# boxer_sensors.net
KiCad netlist of a schematic drawn in Altium Designer
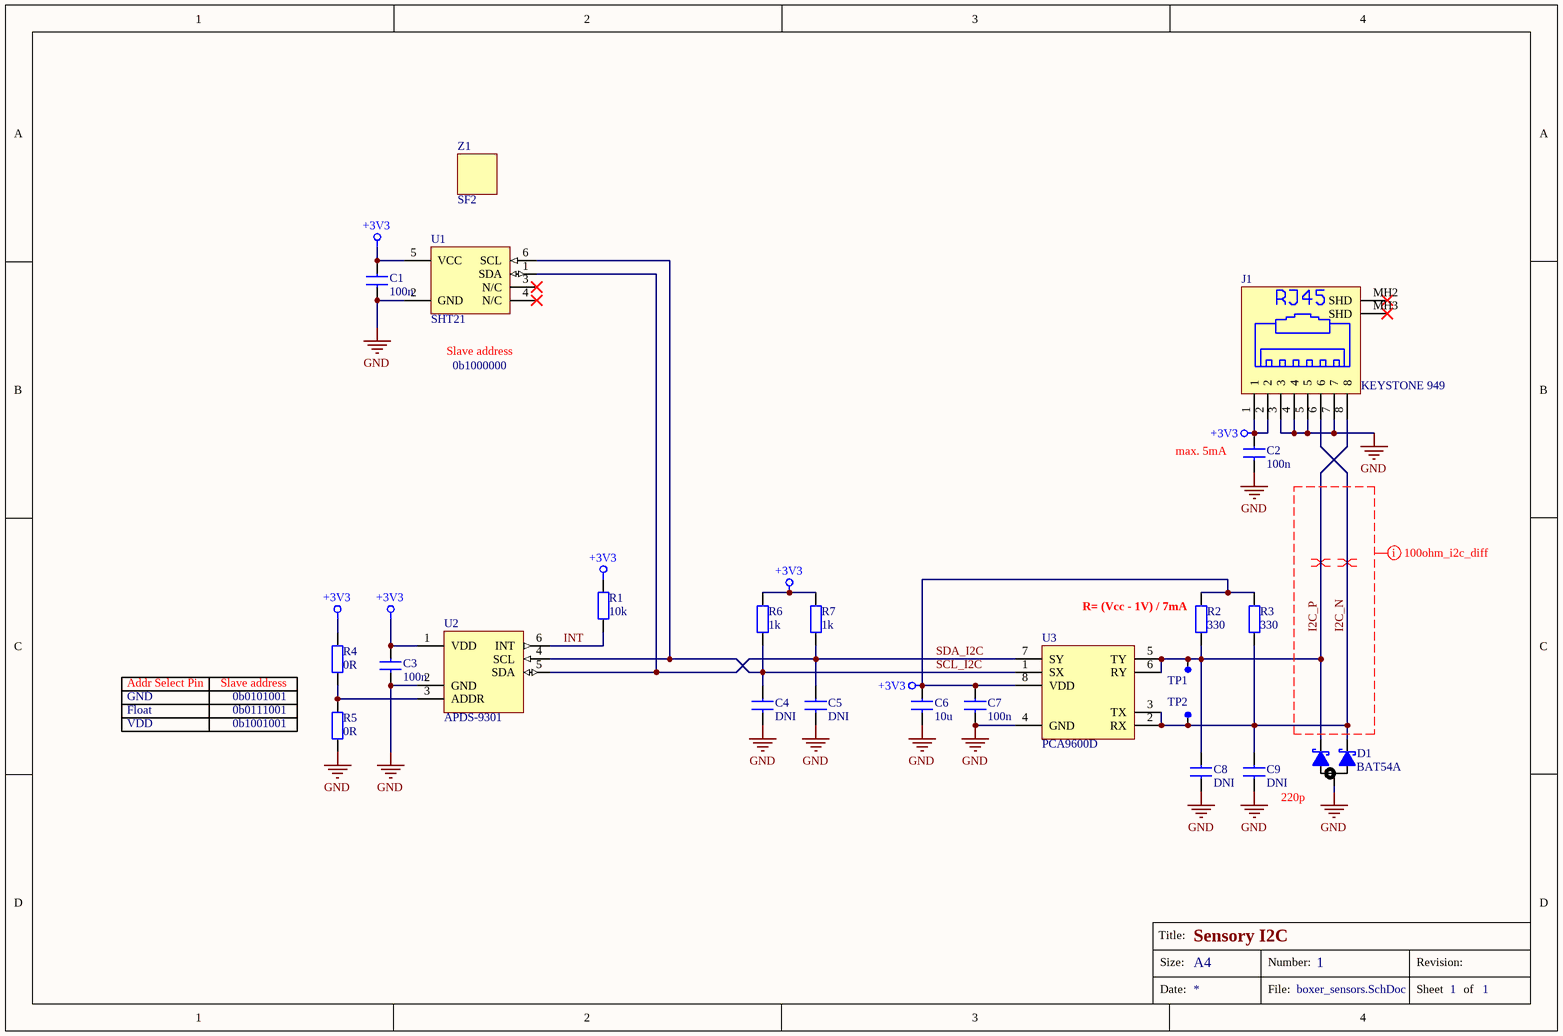
[diagram p0: boxer_sensors.SchDoc]

(export (version "E")
  (design (tool "Eeschema 10.0.6"))
  (components
    (comp (ref "C1")
      (value "100n")
      (footprint "C_0805")
      (description "Capacitor")
      (libsource (lib "boxer_pas") (part "Capacitor"))
    )
    (comp (ref "C2")
      (value "100n")
      (footprint "C_0805")
      (description "Capacitor")
      (libsource (lib "boxer_pas") (part "Capacitor"))
    )
    (comp (ref "C3")
      (value "100n")
      (footprint "C_0805")
      (description "Capacitor")
      (libsource (lib "boxer_pas") (part "Capacitor"))
    )
    (comp (ref "C4")
      (value "DNI")
      (footprint "C_0805")
      (description "Capacitor")
      (libsource (lib "boxer_pas") (part "Capacitor"))
    )
    (comp (ref "C5")
      (value "DNI")
      (footprint "C_0805")
      (description "Capacitor")
      (libsource (lib "boxer_pas") (part "Capacitor"))
    )
    (comp (ref "C6")
      (value "10u")
      (footprint "C_1206")
      (description "Capacitor")
      (libsource (lib "boxer_pas") (part "Capacitor"))
    )
    (comp (ref "C7")
      (value "100n")
      (footprint "C_0805")
      (description "Capacitor")
      (libsource (lib "boxer_pas") (part "Capacitor"))
    )
    (comp (ref "C8")
      (value "DNI")
      (footprint "C_0805")
      (description "Capacitor")
      (libsource (lib "boxer_pas") (part "Capacitor"))
    )
    (comp (ref "C9")
      (value "DNI")
      (footprint "C_0805")
      (description "Capacitor")
      (libsource (lib "boxer_pas") (part "Capacitor"))
    )
    (comp (ref "D1")
      (value "BAT54A")
      (footprint "SOT-23")
      (description "dual Schottky diode common anode")
      (libsource (lib "boxer_pas") (part "Diode Schottky3"))
    )
    (comp (ref "J1")
      (value "KEYSTONE 949")
      (footprint "PN949")
      (description "RJ45 (keystone) Jack, Vertical PCB Mount P/N 949")
      (libsource (lib "boxer_mechanical") (part "RJ45-8"))
    )
    (comp (ref "R1")
      (value "10k")
      (footprint "R_0805")
      (description "Resistor")
      (libsource (lib "boxer_pas") (part "Resistor"))
    )
    (comp (ref "R2")
      (value "330")
      (footprint "R_0805")
      (description "Resistor")
      (libsource (lib "boxer_pas") (part "Resistor"))
    )
    (comp (ref "R3")
      (value "330")
      (footprint "R_0805")
      (description "Resistor")
      (libsource (lib "boxer_pas") (part "Resistor"))
    )
    (comp (ref "R4")
      (value "0R")
      (footprint "R_0805")
      (description "Resistor")
      (libsource (lib "boxer_pas") (part "Resistor"))
    )
    (comp (ref "R5")
      (value "0R")
      (footprint "R_0805")
      (description "Resistor")
      (libsource (lib "boxer_pas") (part "Resistor"))
    )
    (comp (ref "R6")
      (value "1k")
      (footprint "R_0805")
      (description "Resistor")
      (libsource (lib "boxer_pas") (part "Resistor"))
    )
    (comp (ref "R7")
      (value "1k")
      (footprint "R_0805")
      (description "Resistor")
      (libsource (lib "boxer_pas") (part "Resistor"))
    )
    (comp (ref "TP1")
      (value "TEST PAD")
      (footprint "PIN")
      (libsource (lib "boxer_mechanical") (part "TEST_PAD"))
    )
    (comp (ref "TP2")
      (value "TEST PAD")
      (footprint "PIN")
      (libsource (lib "boxer_mechanical") (part "TEST_PAD"))
    )
    (comp (ref "U1")
      (value "SHT21")
      (footprint "DFN6")
      (description "Humidity and Temperature Sensor IC")
      (libsource (lib "boxer_ic") (part "SHT21"))
    )
    (comp (ref "U2")
      (value "APDS-9301")
      (footprint "ChipLED")
      (libsource (lib "boxer_ic") (part "APDS-9301"))
    )
    (comp (ref "U3")
      (value "PCA9600D")
      (footprint "SO8")
      (description "Dual bidirectional I2C bus buffer")
      (libsource (lib "boxer_ic") (part "PCA9600"))
    )
    (comp (ref "Z1")
      (value "SF2")
      (footprint "SF2")
      (description "SF2 Filter Cap  Filter Cap for Humidity &  Temperature Sensors SHT2x")
      (fields (field (name "Comment") "SF2 Filter Cap"))
      (libsource (lib "boxer_mechanical") (part "SF2"))
    )
  )
  (nets
    (net (code "1") (name "+3V3") (class "Default")
      (node (ref "C1") (pin "2") (pinfunction "2_2") (pintype "passive"))
      (node (ref "C2") (pin "2") (pinfunction "2_2") (pintype "passive"))
      (node (ref "C3") (pin "2") (pinfunction "2_2") (pintype "passive"))
      (node (ref "C6") (pin "2") (pinfunction "2_2") (pintype "passive"))
      (node (ref "C7") (pin "2") (pinfunction "2_2") (pintype "passive"))
      (node (ref "J1") (pin "1") (pinfunction "1_1") (pintype "passive"))
      (node (ref "J1") (pin "2") (pinfunction "2_2") (pintype "passive"))
      (node (ref "R1") (pin "2") (pinfunction "2_2") (pintype "passive"))
      (node (ref "R2") (pin "2") (pinfunction "2_2") (pintype "passive"))
      (node (ref "R3") (pin "2") (pinfunction "2_2") (pintype "passive"))
      (node (ref "R4") (pin "2") (pinfunction "2_2") (pintype "passive"))
      (node (ref "R6") (pin "2") (pinfunction "2_2") (pintype "passive"))
      (node (ref "R7") (pin "2") (pinfunction "2_2") (pintype "passive"))
      (node (ref "U1") (pin "5") (pinfunction "VCC_5") (pintype "power_in"))
      (node (ref "U2") (pin "1") (pinfunction "VDD_1") (pintype "power_in"))
      (node (ref "U3") (pin "8") (pinfunction "VDD_8") (pintype "passive"))
    )
    (net (code "2") (name "/I2C_N") (class "Default")
      (node (ref "C9") (pin "2") (pinfunction "2_2") (pintype "passive"))
      (node (ref "D1") (pin "1") (pinfunction "A_1") (pintype "passive"))
      (node (ref "J1") (pin "6") (pinfunction "6_6") (pintype "passive"))
      (node (ref "R3") (pin "1") (pinfunction "1_1") (pintype "passive"))
      (node (ref "TP2") (pin "1") (pinfunction "1_1") (pintype "passive"))
      (node (ref "U3") (pin "2") (pinfunction "RX_2") (pintype "passive"))
      (node (ref "U3") (pin "3") (pinfunction "TX_3") (pintype "passive"))
    )
    (net (code "3") (name "/I2C_P") (class "Default")
      (node (ref "C8") (pin "2") (pinfunction "2_2") (pintype "passive"))
      (node (ref "D1") (pin "2") (pinfunction "A_2") (pintype "passive"))
      (node (ref "J1") (pin "8") (pinfunction "8_8") (pintype "passive"))
      (node (ref "R2") (pin "1") (pinfunction "1_1") (pintype "passive"))
      (node (ref "TP1") (pin "1") (pinfunction "1_1") (pintype "passive"))
      (node (ref "U3") (pin "5") (pinfunction "TY_5") (pintype "passive"))
      (node (ref "U3") (pin "6") (pinfunction "RY_6") (pintype "passive"))
    )
    (net (code "4") (name "/INT") (class "Default")
      (node (ref "R1") (pin "1") (pinfunction "1_1") (pintype "passive"))
      (node (ref "U2") (pin "6") (pinfunction "INT_6") (pintype "output"))
    )
    (net (code "5") (name "/SCL_I2C") (class "Default")
      (node (ref "C4") (pin "2") (pinfunction "2_2") (pintype "passive"))
      (node (ref "R6") (pin "1") (pinfunction "1_1") (pintype "passive"))
      (node (ref "U1") (pin "6") (pinfunction "SCL_6") (pintype "input"))
      (node (ref "U2") (pin "4") (pinfunction "SCL_4") (pintype "input"))
      (node (ref "U3") (pin "1") (pinfunction "SX_1") (pintype "passive"))
    )
    (net (code "6") (name "/SDA_I2C") (class "Default")
      (node (ref "C5") (pin "2") (pinfunction "2_2") (pintype "passive"))
      (node (ref "R7") (pin "1") (pinfunction "1_1") (pintype "passive"))
      (node (ref "U1") (pin "1") (pinfunction "SDA_1") (pintype "bidirectional"))
      (node (ref "U2") (pin "5") (pinfunction "SDA_5") (pintype "bidirectional"))
      (node (ref "U3") (pin "7") (pinfunction "SY_7") (pintype "passive"))
    )
    (net (code "7") (name "GND") (class "Default")
      (node (ref "C1") (pin "1") (pinfunction "1_1") (pintype "passive"))
      (node (ref "C2") (pin "1") (pinfunction "1_1") (pintype "passive"))
      (node (ref "C3") (pin "1") (pinfunction "1_1") (pintype "passive"))
      (node (ref "C4") (pin "1") (pinfunction "1_1") (pintype "passive"))
      (node (ref "C5") (pin "1") (pinfunction "1_1") (pintype "passive"))
      (node (ref "C6") (pin "1") (pinfunction "1_1") (pintype "passive"))
      (node (ref "C7") (pin "1") (pinfunction "1_1") (pintype "passive"))
      (node (ref "C8") (pin "1") (pinfunction "1_1") (pintype "passive"))
      (node (ref "C9") (pin "1") (pinfunction "1_1") (pintype "passive"))
      (node (ref "D1") (pin "3") (pinfunction "K_3") (pintype "passive"))
      (node (ref "J1") (pin "3") (pinfunction "3_3") (pintype "passive"))
      (node (ref "J1") (pin "4") (pinfunction "4_4") (pintype "passive"))
      (node (ref "J1") (pin "5") (pinfunction "5_5") (pintype "passive"))
      (node (ref "J1") (pin "7") (pinfunction "7_7") (pintype "passive"))
      (node (ref "R5") (pin "1") (pinfunction "1_1") (pintype "passive"))
      (node (ref "U1") (pin "2") (pinfunction "GND_2") (pintype "power_in"))
      (node (ref "U2") (pin "2") (pinfunction "GND_2") (pintype "power_in"))
      (node (ref "U3") (pin "4") (pinfunction "GND_4") (pintype "passive"))
    )
    (net (code "8") (name "Net-(U2-ADDR)") (class "Default")
      (node (ref "R4") (pin "1") (pinfunction "1_1") (pintype "passive"))
      (node (ref "R5") (pin "2") (pinfunction "2_2") (pintype "passive"))
      (node (ref "U2") (pin "3") (pinfunction "ADDR_3") (pintype "passive"))
    )
    (net (code "9") (name "unconnected-(J1-SHD-PadMH2)") (class "Default")
      (node (ref "J1") (pin "MH2") (pinfunction "SHD_MH2") (pintype "passive+no_connect"))
    )
    (net (code "10") (name "unconnected-(J1-SHD-PadMH3)") (class "Default")
      (node (ref "J1") (pin "MH3") (pinfunction "SHD_MH3") (pintype "passive+no_connect"))
    )
    (net (code "11") (name "unconnected-(U1-N{slash}C-Pad3)") (class "Default")
      (node (ref "U1") (pin "3") (pinfunction "N/C_3") (pintype "passive+no_connect"))
    )
    (net (code "12") (name "unconnected-(U1-N{slash}C-Pad4)") (class "Default")
      (node (ref "U1") (pin "4") (pinfunction "N/C_4") (pintype "passive+no_connect"))
    )
  )
)
